# noise-and-ring-modulator-v1_0.net
KiCad netlist of a schematic drawn in EAGLE
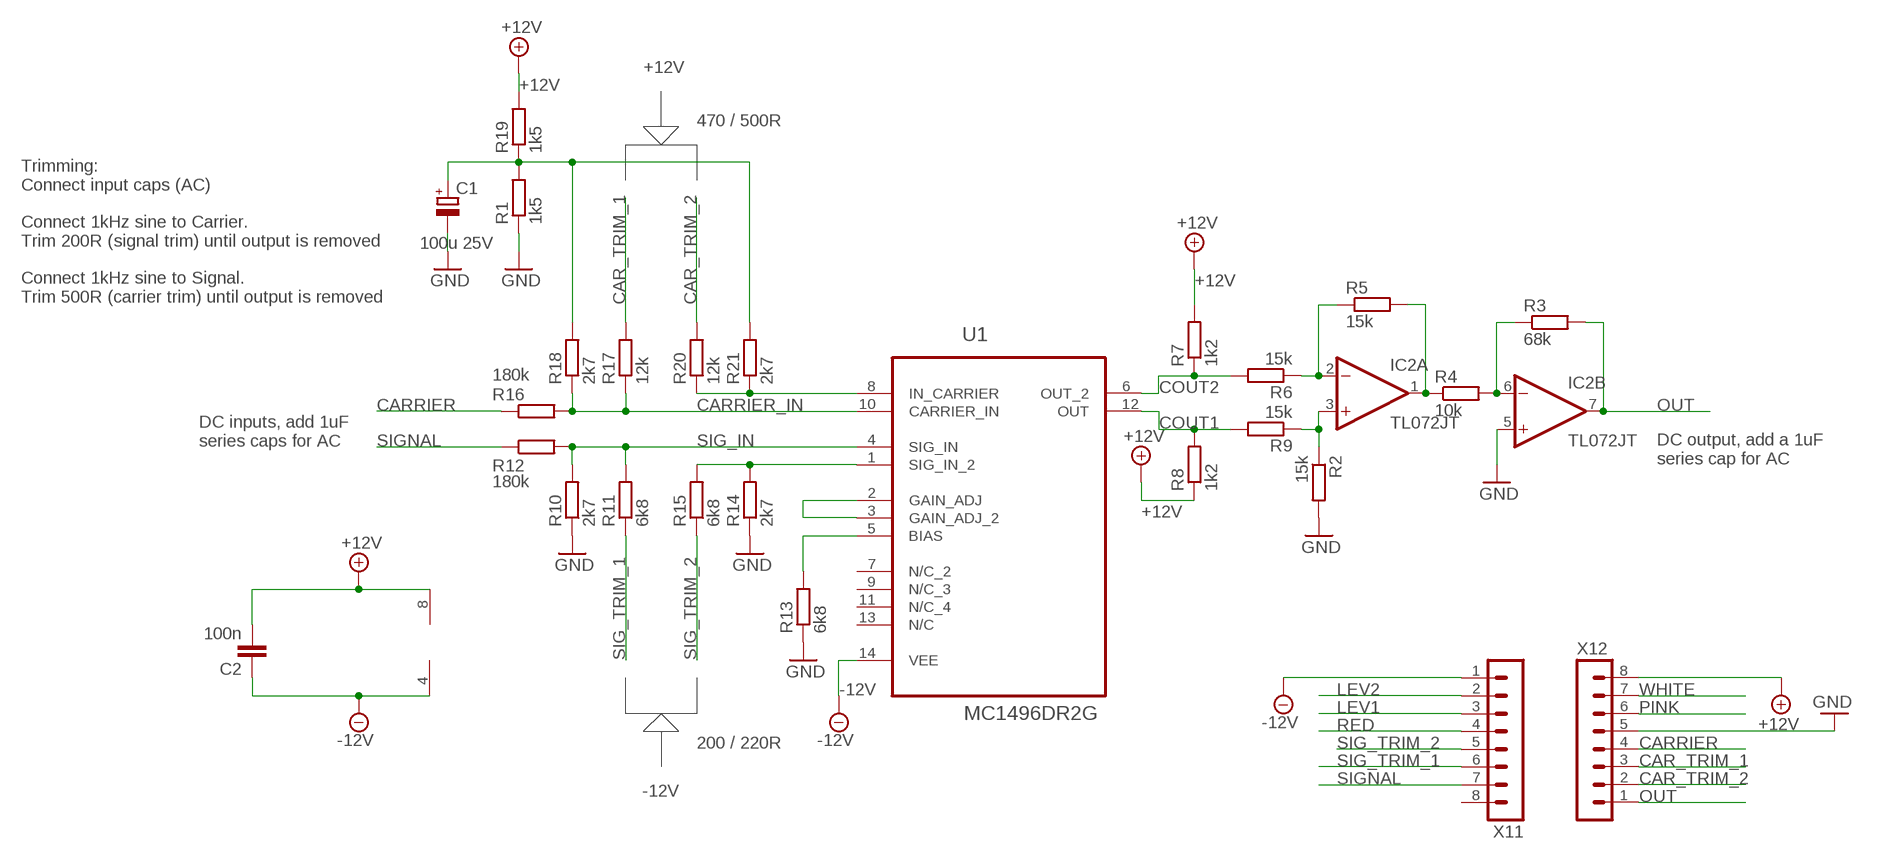
[diagram p0: schematic, sheet 1]
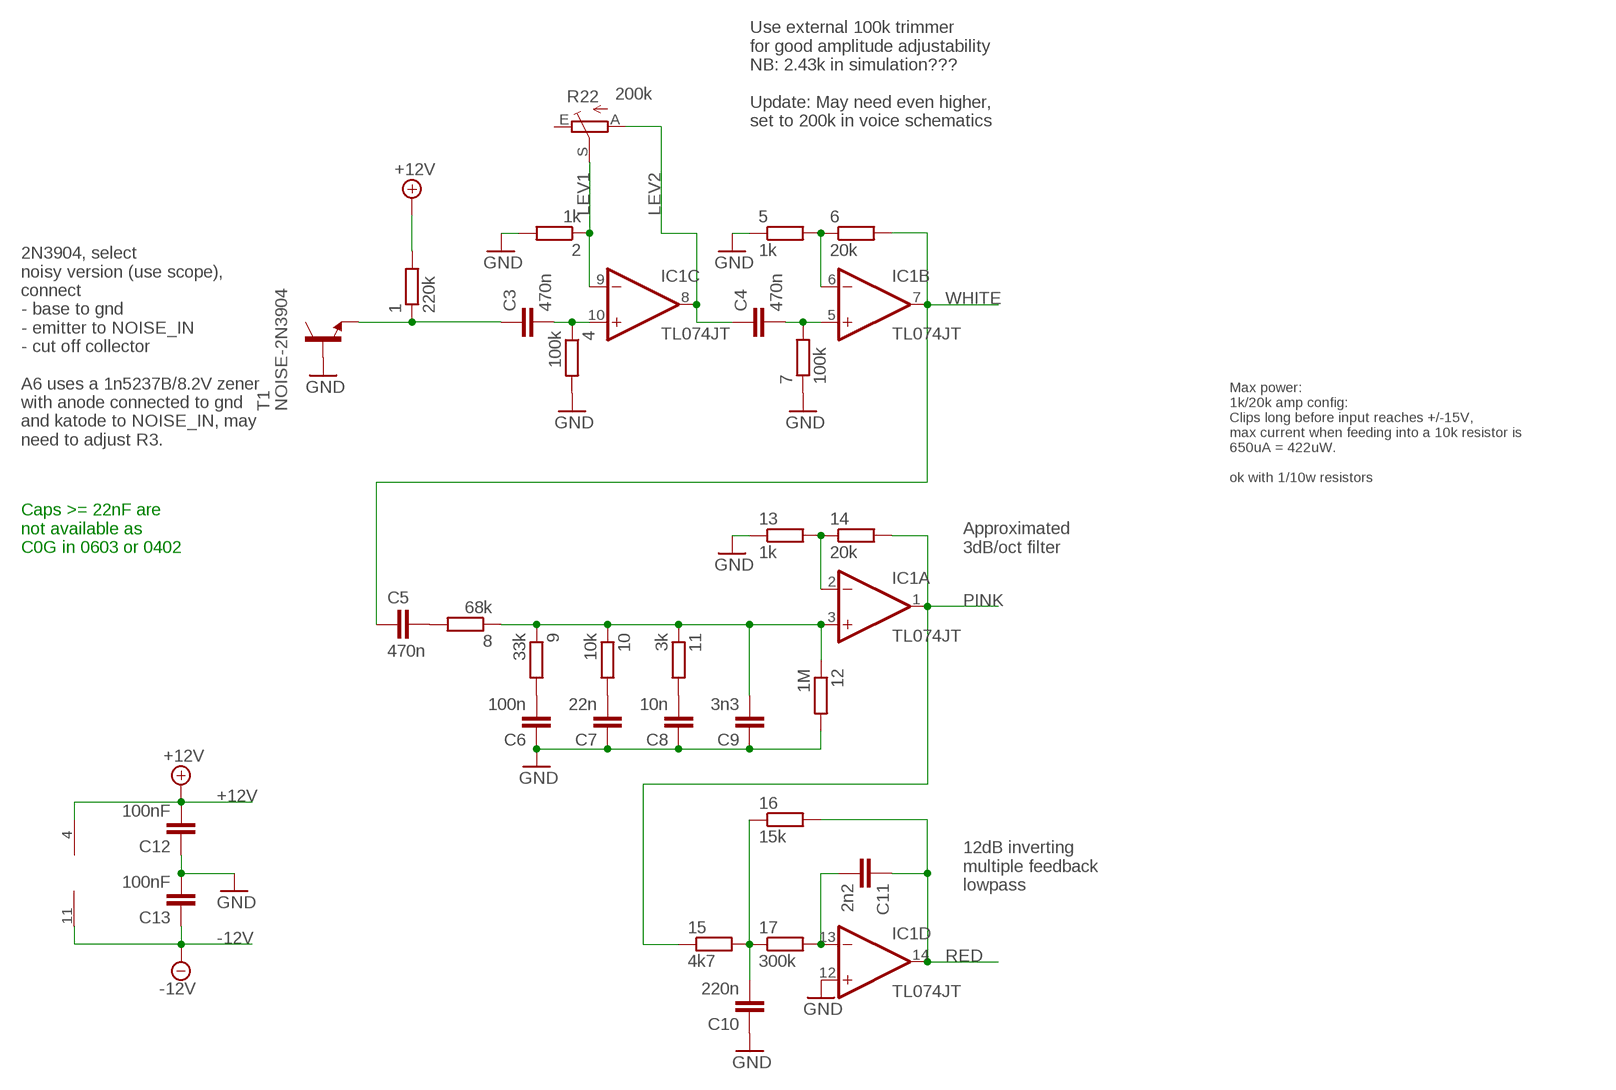
[diagram p1: schematic, sheet 2]

(export (version "E")
  (design (tool "Eeschema 10.0.6"))
  (components
    (comp (ref "1")
      (value "220k")
      (footprint "eagle-import:R0402")
      (libsource (lib "eagle-import") (part "R-EU_R0402"))
    )
    (comp (ref "2")
      (value "1k")
      (footprint "eagle-import:R0402")
      (libsource (lib "eagle-import") (part "R-EU_R0402"))
    )
    (comp (ref "4")
      (value "100k")
      (footprint "eagle-import:R0402")
      (libsource (lib "eagle-import") (part "R-EU_R0402"))
    )
    (comp (ref "5")
      (value "1k")
      (footprint "eagle-import:R0402")
      (libsource (lib "eagle-import") (part "R-EU_R0402"))
    )
    (comp (ref "6")
      (value "20k")
      (footprint "eagle-import:R0402")
      (libsource (lib "eagle-import") (part "R-EU_R0402"))
    )
    (comp (ref "7")
      (value "100k")
      (footprint "eagle-import:R0402")
      (libsource (lib "eagle-import") (part "R-EU_R0402"))
    )
    (comp (ref "8")
      (value "68k")
      (footprint "eagle-import:R0402")
      (libsource (lib "eagle-import") (part "R-EU_R0402"))
    )
    (comp (ref "9")
      (value "33k")
      (footprint "eagle-import:R0402")
      (libsource (lib "eagle-import") (part "R-EU_R0402"))
    )
    (comp (ref "10")
      (value "10k")
      (footprint "eagle-import:R0402")
      (libsource (lib "eagle-import") (part "R-EU_R0402"))
    )
    (comp (ref "11")
      (value "3k")
      (footprint "eagle-import:R0402")
      (libsource (lib "eagle-import") (part "R-EU_R0402"))
    )
    (comp (ref "12")
      (value "1M")
      (footprint "eagle-import:R0402")
      (libsource (lib "eagle-import") (part "R-EU_R0402"))
    )
    (comp (ref "13")
      (value "1k")
      (footprint "eagle-import:R0402")
      (libsource (lib "eagle-import") (part "R-EU_R0402"))
    )
    (comp (ref "14")
      (value "20k")
      (footprint "eagle-import:R0402")
      (libsource (lib "eagle-import") (part "R-EU_R0402"))
    )
    (comp (ref "15")
      (value "4k7")
      (footprint "eagle-import:R0402")
      (libsource (lib "eagle-import") (part "R-EU_R0402"))
    )
    (comp (ref "16")
      (value "15k")
      (footprint "eagle-import:R0402")
      (libsource (lib "eagle-import") (part "R-EU_R0402"))
    )
    (comp (ref "17")
      (value "300k")
      (footprint "eagle-import:R0402")
      (libsource (lib "eagle-import") (part "R-EU_R0402"))
    )
    (comp (ref "C3")
      (value "470n")
      (footprint "eagle-import:C0402-J")
      (libsource (lib "eagle-import") (part "C-EU-J"))
    )
    (comp (ref "C4")
      (value "470n")
      (footprint "eagle-import:C0402-J")
      (libsource (lib "eagle-import") (part "C-EU-J"))
    )
    (comp (ref "C5")
      (value "470n")
      (footprint "eagle-import:C0402-J")
      (libsource (lib "eagle-import") (part "C-EU-J"))
    )
    (comp (ref "C6")
      (value "100n")
      (footprint "eagle-import:C0402-J")
      (libsource (lib "eagle-import") (part "C-EU-J"))
    )
    (comp (ref "C7")
      (value "22n")
      (footprint "eagle-import:C0402-J")
      (libsource (lib "eagle-import") (part "C-EU-J"))
    )
    (comp (ref "C8")
      (value "10n")
      (footprint "eagle-import:C0402-J")
      (libsource (lib "eagle-import") (part "C-EU-J"))
    )
    (comp (ref "C9")
      (value "3n3")
      (footprint "eagle-import:C0402-J")
      (libsource (lib "eagle-import") (part "C-EU-J"))
    )
    (comp (ref "C10")
      (value "220n")
      (footprint "eagle-import:C0402-J")
      (libsource (lib "eagle-import") (part "C-EU-J"))
    )
    (comp (ref "C11")
      (value "2n2")
      (footprint "eagle-import:C0402-J")
      (libsource (lib "eagle-import") (part "C-EU-J"))
    )
    (comp (ref "C12")
      (value "100nF")
      (footprint "eagle-import:C0402-J")
      (libsource (lib "eagle-import") (part "C-EU-J"))
    )
    (comp (ref "C13")
      (value "100nF")
      (footprint "eagle-import:C0402-J")
      (libsource (lib "eagle-import") (part "C-EU-J"))
    )
    (comp (ref "IC1")
      (value "TL074JT")
      (footprint "eagle-import:TSSOP14J")
      (libsource (lib "eagle-import") (part "TL074JT"))
    )
    (comp (ref "R22")
      (value "200k")
      (footprint "eagle-import:S64W")
      (libsource (lib "eagle-import") (part "TRIM_EU-S64W"))
    )
    (comp (ref "T1")
      (value "NOISE-2N3904")
      (footprint "eagle-import:NOISE-2N3904-J")
      (libsource (lib "eagle-import") (part "NOISE-2N3904"))
    )
    (comp (ref "C1")
      (value "100u 25V")
      (footprint "eagle-import:UD-4X5,8_NICHICON")
      (libsource (lib "eagle-import") (part "CPOL-EUUD-4X5,8"))
    )
    (comp (ref "C2")
      (value "100n")
      (footprint "eagle-import:C0402-J")
      (libsource (lib "eagle-import") (part "C-EU-J"))
    )
    (comp (ref "IC2")
      (value "TL072JT")
      (footprint "eagle-import:TSSOP8J")
      (libsource (lib "eagle-import") (part "TL072JT"))
    )
    (comp (ref "R1")
      (value "1k5")
      (footprint "eagle-import:R0402")
      (libsource (lib "eagle-import") (part "R-EU_R0402"))
    )
    (comp (ref "R2")
      (value "15k")
      (footprint "eagle-import:R0402")
      (libsource (lib "eagle-import") (part "R-EU_R0402"))
    )
    (comp (ref "R3")
      (value "68k")
      (footprint "eagle-import:R0402")
      (libsource (lib "eagle-import") (part "R-EU_R0402"))
    )
    (comp (ref "R4")
      (value "10k")
      (footprint "eagle-import:R0402")
      (libsource (lib "eagle-import") (part "R-EU_R0402"))
    )
    (comp (ref "R5")
      (value "15k")
      (footprint "eagle-import:R0402")
      (libsource (lib "eagle-import") (part "R-EU_R0402"))
    )
    (comp (ref "R6")
      (value "15k")
      (footprint "eagle-import:R0402")
      (libsource (lib "eagle-import") (part "R-EU_R0402"))
    )
    (comp (ref "R7")
      (value "1k2")
      (footprint "eagle-import:R0402")
      (libsource (lib "eagle-import") (part "R-EU_R0402"))
    )
    (comp (ref "R8")
      (value "1k2")
      (footprint "eagle-import:R0402")
      (libsource (lib "eagle-import") (part "R-EU_R0402"))
    )
    (comp (ref "R9")
      (value "15k")
      (footprint "eagle-import:R0402")
      (libsource (lib "eagle-import") (part "R-EU_R0402"))
    )
    (comp (ref "R10")
      (value "2k7")
      (footprint "eagle-import:R0402")
      (libsource (lib "eagle-import") (part "R-EU_R0402"))
    )
    (comp (ref "R11")
      (value "6k8")
      (footprint "eagle-import:R0402")
      (libsource (lib "eagle-import") (part "R-EU_R0402"))
    )
    (comp (ref "R12")
      (value "180k")
      (footprint "eagle-import:R0402")
      (libsource (lib "eagle-import") (part "R-EU_R0402"))
    )
    (comp (ref "R13")
      (value "6k8")
      (footprint "eagle-import:R0402")
      (libsource (lib "eagle-import") (part "R-EU_R0402"))
    )
    (comp (ref "R14")
      (value "2k7")
      (footprint "eagle-import:R0402")
      (libsource (lib "eagle-import") (part "R-EU_R0402"))
    )
    (comp (ref "R15")
      (value "6k8")
      (footprint "eagle-import:R0402")
      (libsource (lib "eagle-import") (part "R-EU_R0402"))
    )
    (comp (ref "R16")
      (value "180k")
      (footprint "eagle-import:R0402")
      (libsource (lib "eagle-import") (part "R-EU_R0402"))
    )
    (comp (ref "R17")
      (value "12k")
      (footprint "eagle-import:R0402")
      (libsource (lib "eagle-import") (part "R-EU_R0402"))
    )
    (comp (ref "R18")
      (value "2k7")
      (footprint "eagle-import:R0402")
      (libsource (lib "eagle-import") (part "R-EU_R0402"))
    )
    (comp (ref "R19")
      (value "1k5")
      (footprint "eagle-import:R0402")
      (libsource (lib "eagle-import") (part "R-EU_R0402"))
    )
    (comp (ref "R20")
      (value "12k")
      (footprint "eagle-import:R0402")
      (libsource (lib "eagle-import") (part "R-EU_R0402"))
    )
    (comp (ref "R21")
      (value "2k7")
      (footprint "eagle-import:R0402")
      (libsource (lib "eagle-import") (part "R-EU_R0402"))
    )
    (comp (ref "U1")
      (value "MC1496DR2G")
      (footprint "eagle-import:SOIC127P600X175-14N")
      (libsource (lib "eagle-import") (part "MC1496DR2G"))
    )
    (comp (ref "X11")
      (value "MA08-1JN")
      (footprint "eagle-import:MA08N-1J")
      (libsource (lib "eagle-import") (part "MA08-1JN"))
    )
    (comp (ref "X12")
      (value "MA08-1JN")
      (footprint "eagle-import:MA08N-1J")
      (libsource (lib "eagle-import") (part "MA08-1JN"))
    )
  )
  (nets
    (net (code "1") (name "+12V") (class "Default")
      (node (ref "1") (pin "2") (pinfunction "2_2") (pintype "passive"))
      (node (ref "C12") (pin "2") (pinfunction "2_2") (pintype "passive"))
      (node (ref "C2") (pin "2") (pinfunction "2_2") (pintype "passive"))
      (node (ref "IC1") (pin "4") (pinfunction "V+_4") (pintype "power_in"))
      (node (ref "IC2") (pin "8") (pinfunction "V+_8") (pintype "power_in"))
      (node (ref "R19") (pin "2") (pinfunction "2_2") (pintype "passive"))
      (node (ref "R7") (pin "2") (pinfunction "2_2") (pintype "passive"))
      (node (ref "R8") (pin "1") (pinfunction "1_1") (pintype "passive"))
      (node (ref "X12") (pin "8") (pinfunction "8_8") (pintype "passive"))
    )
    (net (code "2") (name "-12V") (class "Default")
      (node (ref "C13") (pin "1") (pinfunction "1_1") (pintype "passive"))
      (node (ref "C2") (pin "1") (pinfunction "1_1") (pintype "passive"))
      (node (ref "IC1") (pin "11") (pinfunction "V-_11") (pintype "power_in"))
      (node (ref "IC2") (pin "4") (pinfunction "V-_4") (pintype "power_in"))
      (node (ref "U1") (pin "14") (pinfunction "VEE_14") (pintype "passive"))
      (node (ref "X11") (pin "1") (pinfunction "1_1") (pintype "passive"))
    )
    (net (code "3") (name "CARRIER") (class "Default")
      (node (ref "R16") (pin "1") (pinfunction "1_1") (pintype "passive"))
      (node (ref "X12") (pin "4") (pinfunction "4_4") (pintype "passive"))
    )
    (net (code "4") (name "CARRIER_IN") (class "Default")
      (node (ref "R16") (pin "2") (pinfunction "2_2") (pintype "passive"))
      (node (ref "R17") (pin "1") (pinfunction "1_1") (pintype "passive"))
      (node (ref "R18") (pin "1") (pinfunction "1_1") (pintype "passive"))
      (node (ref "U1") (pin "10") (pinfunction "CARRIER_IN_10") (pintype "power_in"))
    )
    (net (code "5") (name "CAR_TRIM_1") (class "Default")
      (node (ref "R17") (pin "2") (pinfunction "2_2") (pintype "passive"))
      (node (ref "X12") (pin "3") (pinfunction "3_3") (pintype "passive"))
    )
    (net (code "6") (name "CAR_TRIM_2") (class "Default")
      (node (ref "R20") (pin "2") (pinfunction "2_2") (pintype "passive"))
      (node (ref "X12") (pin "2") (pinfunction "2_2") (pintype "passive"))
    )
    (net (code "7") (name "COUT1") (class "Default")
      (node (ref "R8") (pin "2") (pinfunction "2_2") (pintype "passive"))
      (node (ref "R9") (pin "2") (pinfunction "2_2") (pintype "passive"))
      (node (ref "U1") (pin "12") (pinfunction "OUT_12") (pintype "output"))
    )
    (net (code "8") (name "COUT2") (class "Default")
      (node (ref "R6") (pin "2") (pinfunction "2_2") (pintype "passive"))
      (node (ref "R7") (pin "1") (pinfunction "1_1") (pintype "passive"))
      (node (ref "U1") (pin "6") (pinfunction "OUT_2_6") (pintype "output"))
    )
    (net (code "9") (name "GND") (class "Default")
      (node (ref "12") (pin "2") (pinfunction "2_2") (pintype "passive"))
      (node (ref "13") (pin "1") (pinfunction "1_1") (pintype "passive"))
      (node (ref "2") (pin "2") (pinfunction "2_2") (pintype "passive"))
      (node (ref "4") (pin "2") (pinfunction "2_2") (pintype "passive"))
      (node (ref "5") (pin "1") (pinfunction "1_1") (pintype "passive"))
      (node (ref "7") (pin "1") (pinfunction "1_1") (pintype "passive"))
      (node (ref "C1") (pin "-") (pinfunction "-_-") (pintype "passive"))
      (node (ref "C10") (pin "1") (pinfunction "1_1") (pintype "passive"))
      (node (ref "C12") (pin "1") (pinfunction "1_1") (pintype "passive"))
      (node (ref "C13") (pin "2") (pinfunction "2_2") (pintype "passive"))
      (node (ref "C6") (pin "1") (pinfunction "1_1") (pintype "passive"))
      (node (ref "C7") (pin "1") (pinfunction "1_1") (pintype "passive"))
      (node (ref "C8") (pin "1") (pinfunction "1_1") (pintype "passive"))
      (node (ref "C9") (pin "1") (pinfunction "1_1") (pintype "passive"))
      (node (ref "IC1") (pin "12") (pinfunction "+IN_12") (pintype "input"))
      (node (ref "IC2") (pin "5") (pinfunction "+IN_5") (pintype "input"))
      (node (ref "R1") (pin "1") (pinfunction "1_1") (pintype "passive"))
      (node (ref "R10") (pin "1") (pinfunction "1_1") (pintype "passive"))
      (node (ref "R13") (pin "1") (pinfunction "1_1") (pintype "passive"))
      (node (ref "R14") (pin "1") (pinfunction "1_1") (pintype "passive"))
      (node (ref "R2") (pin "2") (pinfunction "2_2") (pintype "passive"))
      (node (ref "T1") (pin "B") (pinfunction "B_B") (pintype "passive"))
      (node (ref "X12") (pin "5") (pinfunction "5_5") (pintype "passive"))
    )
    (net (code "10") (name "LEV1") (class "Default")
      (node (ref "2") (pin "1") (pinfunction "1_1") (pintype "passive"))
      (node (ref "IC1") (pin "9") (pinfunction "-IN_9") (pintype "input"))
      (node (ref "R22") (pin "S") (pinfunction "S_S") (pintype "passive"))
      (node (ref "X11") (pin "3") (pinfunction "3_3") (pintype "passive"))
    )
    (net (code "11") (name "LEV2") (class "Default")
      (node (ref "C4") (pin "1") (pinfunction "1_1") (pintype "passive"))
      (node (ref "IC1") (pin "8") (pinfunction "OUT_8") (pintype "output"))
      (node (ref "R22") (pin "A") (pinfunction "A_A") (pintype "passive"))
      (node (ref "X11") (pin "2") (pinfunction "2_2") (pintype "passive"))
    )
    (net (code "12") (name "Net-(1-Pad1)") (class "Default")
      (node (ref "1") (pin "1") (pinfunction "1_1") (pintype "passive"))
      (node (ref "C3") (pin "1") (pinfunction "1_1") (pintype "passive"))
      (node (ref "T1") (pin "E") (pinfunction "E_E") (pintype "passive"))
    )
    (net (code "13") (name "Net-(8-Pad2)") (class "Default")
      (node (ref "8") (pin "2") (pinfunction "2_2") (pintype "passive"))
      (node (ref "C5") (pin "2") (pinfunction "2_2") (pintype "passive"))
    )
    (net (code "14") (name "Net-(9-Pad2)") (class "Default")
      (node (ref "9") (pin "2") (pinfunction "2_2") (pintype "passive"))
      (node (ref "C6") (pin "2") (pinfunction "2_2") (pintype "passive"))
    )
    (net (code "15") (name "Net-(10-Pad2)") (class "Default")
      (node (ref "10") (pin "2") (pinfunction "2_2") (pintype "passive"))
      (node (ref "C7") (pin "2") (pinfunction "2_2") (pintype "passive"))
    )
    (net (code "16") (name "Net-(11-Pad2)") (class "Default")
      (node (ref "11") (pin "2") (pinfunction "2_2") (pintype "passive"))
      (node (ref "C8") (pin "2") (pinfunction "2_2") (pintype "passive"))
    )
    (net (code "17") (name "Net-(15-Pad2)") (class "Default")
      (node (ref "15") (pin "2") (pinfunction "2_2") (pintype "passive"))
      (node (ref "16") (pin "1") (pinfunction "1_1") (pintype "passive"))
      (node (ref "17") (pin "1") (pinfunction "1_1") (pintype "passive"))
      (node (ref "C10") (pin "2") (pinfunction "2_2") (pintype "passive"))
    )
    (net (code "18") (name "Net-(C1-Pad+)") (class "Default")
      (node (ref "C1") (pin "+") (pinfunction "+_+") (pintype "passive"))
      (node (ref "R1") (pin "2") (pinfunction "2_2") (pintype "passive"))
      (node (ref "R18") (pin "2") (pinfunction "2_2") (pintype "passive"))
      (node (ref "R19") (pin "1") (pinfunction "1_1") (pintype "passive"))
      (node (ref "R21") (pin "2") (pinfunction "2_2") (pintype "passive"))
    )
    (net (code "19") (name "Net-(IC1A-+IN)") (class "Default")
      (node (ref "10") (pin "1") (pinfunction "1_1") (pintype "passive"))
      (node (ref "11") (pin "1") (pinfunction "1_1") (pintype "passive"))
      (node (ref "12") (pin "1") (pinfunction "1_1") (pintype "passive"))
      (node (ref "8") (pin "1") (pinfunction "1_1") (pintype "passive"))
      (node (ref "9") (pin "1") (pinfunction "1_1") (pintype "passive"))
      (node (ref "C9") (pin "2") (pinfunction "2_2") (pintype "passive"))
      (node (ref "IC1") (pin "3") (pinfunction "+IN_3") (pintype "input"))
    )
    (net (code "20") (name "Net-(IC1A--IN)") (class "Default")
      (node (ref "13") (pin "2") (pinfunction "2_2") (pintype "passive"))
      (node (ref "14") (pin "1") (pinfunction "1_1") (pintype "passive"))
      (node (ref "IC1") (pin "2") (pinfunction "-IN_2") (pintype "input"))
    )
    (net (code "21") (name "Net-(IC1B-+IN)") (class "Default")
      (node (ref "7") (pin "2") (pinfunction "2_2") (pintype "passive"))
      (node (ref "C4") (pin "2") (pinfunction "2_2") (pintype "passive"))
      (node (ref "IC1") (pin "5") (pinfunction "+IN_5") (pintype "input"))
    )
    (net (code "22") (name "Net-(IC1B--IN)") (class "Default")
      (node (ref "5") (pin "2") (pinfunction "2_2") (pintype "passive"))
      (node (ref "6") (pin "1") (pinfunction "1_1") (pintype "passive"))
      (node (ref "IC1") (pin "6") (pinfunction "-IN_6") (pintype "input"))
    )
    (net (code "23") (name "Net-(IC1C-+IN)") (class "Default")
      (node (ref "4") (pin "1") (pinfunction "1_1") (pintype "passive"))
      (node (ref "C3") (pin "2") (pinfunction "2_2") (pintype "passive"))
      (node (ref "IC1") (pin "10") (pinfunction "+IN_10") (pintype "input"))
    )
    (net (code "24") (name "Net-(IC1D--IN)") (class "Default")
      (node (ref "17") (pin "2") (pinfunction "2_2") (pintype "passive"))
      (node (ref "C11") (pin "2") (pinfunction "2_2") (pintype "passive"))
      (node (ref "IC1") (pin "13") (pinfunction "-IN_13") (pintype "input"))
    )
    (net (code "25") (name "Net-(IC2A-+IN)") (class "Default")
      (node (ref "IC2") (pin "3") (pinfunction "+IN_3") (pintype "input"))
      (node (ref "R2") (pin "1") (pinfunction "1_1") (pintype "passive"))
      (node (ref "R9") (pin "1") (pinfunction "1_1") (pintype "passive"))
    )
    (net (code "26") (name "Net-(IC2A--IN)") (class "Default")
      (node (ref "IC2") (pin "2") (pinfunction "-IN_2") (pintype "input"))
      (node (ref "R5") (pin "1") (pinfunction "1_1") (pintype "passive"))
      (node (ref "R6") (pin "1") (pinfunction "1_1") (pintype "passive"))
    )
    (net (code "27") (name "Net-(IC2A-OUT)") (class "Default")
      (node (ref "IC2") (pin "1") (pinfunction "OUT_1") (pintype "output"))
      (node (ref "R4") (pin "1") (pinfunction "1_1") (pintype "passive"))
      (node (ref "R5") (pin "2") (pinfunction "2_2") (pintype "passive"))
    )
    (net (code "28") (name "Net-(IC2B--IN)") (class "Default")
      (node (ref "IC2") (pin "6") (pinfunction "-IN_6") (pintype "input"))
      (node (ref "R3") (pin "1") (pinfunction "1_1") (pintype "passive"))
      (node (ref "R4") (pin "2") (pinfunction "2_2") (pintype "passive"))
    )
    (net (code "29") (name "Net-(U1-BIAS)") (class "Default")
      (node (ref "R13") (pin "2") (pinfunction "2_2") (pintype "passive"))
      (node (ref "U1") (pin "5") (pinfunction "BIAS_5") (pintype "input"))
    )
    (net (code "30") (name "Net-(U1-GAIN_ADJ)") (class "Default")
      (node (ref "U1") (pin "2") (pinfunction "GAIN_ADJ_2") (pintype "input"))
      (node (ref "U1") (pin "3") (pinfunction "GAIN_ADJ_2_3") (pintype "input"))
    )
    (net (code "31") (name "Net-(U1-IN_CARRIER)") (class "Default")
      (node (ref "R20") (pin "1") (pinfunction "1_1") (pintype "passive"))
      (node (ref "R21") (pin "1") (pinfunction "1_1") (pintype "passive"))
      (node (ref "U1") (pin "8") (pinfunction "IN_CARRIER_8") (pintype "power_in"))
    )
    (net (code "32") (name "Net-(U1-SIG_IN_2)") (class "Default")
      (node (ref "R14") (pin "2") (pinfunction "2_2") (pintype "passive"))
      (node (ref "R15") (pin "2") (pinfunction "2_2") (pintype "passive"))
      (node (ref "U1") (pin "1") (pinfunction "SIG_IN_2_1") (pintype "input"))
    )
    (net (code "33") (name "OUT") (class "Default")
      (node (ref "IC2") (pin "7") (pinfunction "OUT_7") (pintype "output"))
      (node (ref "R3") (pin "2") (pinfunction "2_2") (pintype "passive"))
      (node (ref "X12") (pin "1") (pinfunction "1_1") (pintype "passive"))
    )
    (net (code "34") (name "PINK") (class "Default")
      (node (ref "14") (pin "2") (pinfunction "2_2") (pintype "passive"))
      (node (ref "15") (pin "1") (pinfunction "1_1") (pintype "passive"))
      (node (ref "IC1") (pin "1") (pinfunction "OUT_1") (pintype "output"))
      (node (ref "X12") (pin "6") (pinfunction "6_6") (pintype "passive"))
    )
    (net (code "35") (name "RED") (class "Default")
      (node (ref "16") (pin "2") (pinfunction "2_2") (pintype "passive"))
      (node (ref "C11") (pin "1") (pinfunction "1_1") (pintype "passive"))
      (node (ref "IC1") (pin "14") (pinfunction "OUT_14") (pintype "output"))
      (node (ref "X11") (pin "4") (pinfunction "4_4") (pintype "passive"))
    )
    (net (code "36") (name "SIGNAL") (class "Default")
      (node (ref "R12") (pin "1") (pinfunction "1_1") (pintype "passive"))
      (node (ref "X11") (pin "7") (pinfunction "7_7") (pintype "passive"))
    )
    (net (code "37") (name "SIG_IN") (class "Default")
      (node (ref "R10") (pin "2") (pinfunction "2_2") (pintype "passive"))
      (node (ref "R11") (pin "2") (pinfunction "2_2") (pintype "passive"))
      (node (ref "R12") (pin "2") (pinfunction "2_2") (pintype "passive"))
      (node (ref "U1") (pin "4") (pinfunction "SIG_IN_4") (pintype "input"))
    )
    (net (code "38") (name "SIG_TRIM_1") (class "Default")
      (node (ref "R11") (pin "1") (pinfunction "1_1") (pintype "passive"))
      (node (ref "X11") (pin "6") (pinfunction "6_6") (pintype "passive"))
    )
    (net (code "39") (name "SIG_TRIM_2") (class "Default")
      (node (ref "R15") (pin "1") (pinfunction "1_1") (pintype "passive"))
      (node (ref "X11") (pin "5") (pinfunction "5_5") (pintype "passive"))
    )
    (net (code "40") (name "WHITE") (class "Default")
      (node (ref "6") (pin "2") (pinfunction "2_2") (pintype "passive"))
      (node (ref "C5") (pin "1") (pinfunction "1_1") (pintype "passive"))
      (node (ref "IC1") (pin "7") (pinfunction "OUT_7") (pintype "output"))
      (node (ref "X12") (pin "7") (pinfunction "7_7") (pintype "passive"))
    )
    (net (code "41") (name "unconnected-(R22-PadE)") (class "Default")
      (node (ref "R22") (pin "E") (pinfunction "E_E") (pintype "passive"))
    )
    (net (code "42") (name "unconnected-(U1-N{slash}C-Pad13)") (class "Default")
      (node (ref "U1") (pin "13") (pinfunction "N/C_13") (pintype "no_connect"))
    )
    (net (code "43") (name "unconnected-(U1-N{slash}C_2-Pad7)") (class "Default")
      (node (ref "U1") (pin "7") (pinfunction "N/C_2_7") (pintype "no_connect"))
    )
    (net (code "44") (name "unconnected-(U1-N{slash}C_3-Pad9)") (class "Default")
      (node (ref "U1") (pin "9") (pinfunction "N/C_3_9") (pintype "no_connect"))
    )
    (net (code "45") (name "unconnected-(U1-N{slash}C_4-Pad11)") (class "Default")
      (node (ref "U1") (pin "11") (pinfunction "N/C_4_11") (pintype "no_connect"))
    )
    (net (code "46") (name "unconnected-(X11-Pad8)") (class "Default")
      (node (ref "X11") (pin "8") (pinfunction "8_8") (pintype "passive"))
    )
  )
)
